# SiPM.net
KiCad netlist of a schematic drawn in EAGLE
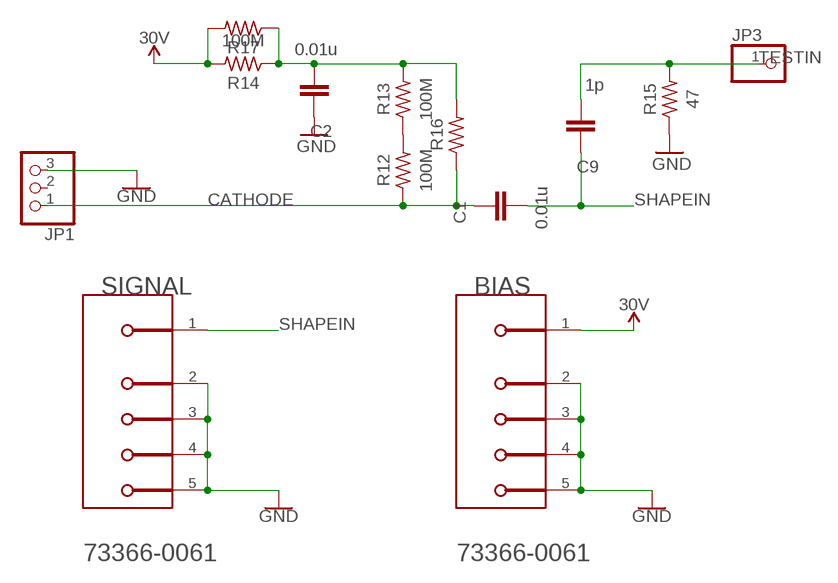
[diagram p0: schematic, sheet 1]

(export (version "E")
  (design (tool "Eeschema 10.0.6"))
  (components
    (comp (ref "BIAS")
      (value "MOLEX_73366-0061MOLEX_73366-0061_0_0")
      (footprint "eagle-import:MOLEX_73366-0061_0")
      (fields
        (field (name "DIGIKEY_PART_NUMBER") "WM5541-ND")
        (field (name "MF") "Molex")
        (field (name "MOUSER_PART_NUMBER") "538-73366-0061")
      )
      (libsource (lib "eagle-import") (part "MOLEX_73366-0061MOLEX_73366-0061_0_0"))
    )
    (comp (ref "C1")
      (value "0.01u")
      (footprint "eagle-import:CAP_1206")
      (fields
        (field (name "DIGIKEY_PART_NUMBER") "GRM31CR60J107ME39L")
        (field (name "MANUFACTURER") "Murata Electronics North America")
        (field (name "CREATED_BY") "PCBLayout.com")
      )
      (libsource (lib "eagle-import") (part "GRM31CR60J107ME39L"))
    )
    (comp (ref "C2")
      (value "0.01u")
      (footprint "eagle-import:CAP_1206")
      (fields
        (field (name "DIGIKEY_PART_NUMBER") "GRM31CR60J107ME39L")
        (field (name "MANUFACTURER") "Murata Electronics North America")
        (field (name "CREATED_BY") "PCBLayout.com")
      )
      (libsource (lib "eagle-import") (part "GRM31CR60J107ME39L"))
    )
    (comp (ref "C9")
      (value "1p")
      (footprint "eagle-import:CAP_1206")
      (fields
        (field (name "DIGIKEY_PART_NUMBER") "GRM31CR60J107ME39L")
        (field (name "MANUFACTURER") "Murata Electronics North America")
        (field (name "CREATED_BY") "PCBLayout.com")
      )
      (libsource (lib "eagle-import") (part "GRM31CR60J107ME39L"))
    )
    (comp (ref "JP1")
      (value "PINHD-1X3")
      (footprint "eagle-import:1X03")
      (libsource (lib "eagle-import") (part "PINHD-1X3"))
    )
    (comp (ref "JP3")
      (value "PINHD-1X1")
      (footprint "eagle-import:1X01")
      (libsource (lib "eagle-import") (part "PINHD-1X1"))
    )
    (comp (ref "R12")
      (value "100M")
      (footprint "eagle-import:RESAD1176W63L850D250B")
      (libsource (lib "eagle-import") (part "R-USAXIAL-11.7MM-PITCH_"))
    )
    (comp (ref "R13")
      (value "100M")
      (footprint "eagle-import:RESAD1176W63L850D250B")
      (libsource (lib "eagle-import") (part "R-USAXIAL-11.7MM-PITCH_"))
    )
    (comp (ref "R14")
      (value "100M")
      (footprint "eagle-import:RESAD1176W63L850D250B")
      (libsource (lib "eagle-import") (part "R-USAXIAL-11.7MM-PITCH_"))
    )
    (comp (ref "R15")
      (value "47")
      (footprint "eagle-import:RESAD1176W63L850D250B")
      (libsource (lib "eagle-import") (part "R-USAXIAL-11.7MM-PITCH_"))
    )
    (comp (ref "R16")
      (value "R-US_AXIAL-11.7MM-PITCH")
      (footprint "eagle-import:RESAD1176W63L850D250B")
      (libsource (lib "eagle-import") (part "R-USAXIAL-11.7MM-PITCH_"))
    )
    (comp (ref "R17")
      (value "R-US_AXIAL-11.7MM-PITCH")
      (footprint "eagle-import:RESAD1176W63L850D250B")
      (libsource (lib "eagle-import") (part "R-USAXIAL-11.7MM-PITCH_"))
    )
    (comp (ref "SIGNAL")
      (value "MOLEX_73366-0061MOLEX_73366-0061_0_0")
      (footprint "eagle-import:MOLEX_73366-0061_0")
      (fields
        (field (name "DIGIKEY_PART_NUMBER") "WM5541-ND")
        (field (name "MF") "Molex")
        (field (name "MOUSER_PART_NUMBER") "538-73366-0061")
      )
      (libsource (lib "eagle-import") (part "MOLEX_73366-0061MOLEX_73366-0061_0_0"))
    )
  )
  (nets
    (net (code "1") (name "/CATHODE") (class "Default")
      (node (ref "C1") (pin "1") (pinfunction "1_1") (pintype "passive"))
      (node (ref "JP1") (pin "1") (pinfunction "1_1") (pintype "passive"))
      (node (ref "R12") (pin "1") (pinfunction "1_1") (pintype "passive"))
      (node (ref "R16") (pin "1") (pinfunction "1_1") (pintype "passive"))
    )
    (net (code "2") (name "/SHAPEIN") (class "Default")
      (node (ref "C1") (pin "2") (pinfunction "2_2") (pintype "passive"))
      (node (ref "C9") (pin "1") (pinfunction "1_1") (pintype "passive"))
      (node (ref "SIGNAL") (pin "1") (pinfunction "1_1") (pintype "passive"))
    )
    (net (code "3") (name "/TESTIN") (class "Default")
      (node (ref "C9") (pin "2") (pinfunction "2_2") (pintype "passive"))
      (node (ref "JP3") (pin "1") (pinfunction "1_1") (pintype "passive"))
      (node (ref "R15") (pin "2") (pinfunction "2_2") (pintype "passive"))
    )
    (net (code "4") (name "30V") (class "Default")
      (node (ref "BIAS") (pin "1") (pinfunction "1_1") (pintype "passive"))
      (node (ref "R14") (pin "2") (pinfunction "2_2") (pintype "passive"))
      (node (ref "R17") (pin "2") (pinfunction "2_2") (pintype "passive"))
    )
    (net (code "5") (name "GND") (class "Default")
      (node (ref "BIAS") (pin "2") (pinfunction "MNT_1_2") (pintype "passive"))
      (node (ref "BIAS") (pin "3") (pinfunction "MNT_2_3") (pintype "passive"))
      (node (ref "BIAS") (pin "4") (pinfunction "MNT_3_4") (pintype "passive"))
      (node (ref "BIAS") (pin "5") (pinfunction "MNT_4_5") (pintype "passive"))
      (node (ref "C2") (pin "1") (pinfunction "1_1") (pintype "passive"))
      (node (ref "JP1") (pin "3") (pinfunction "3_3") (pintype "passive"))
      (node (ref "R15") (pin "1") (pinfunction "1_1") (pintype "passive"))
      (node (ref "SIGNAL") (pin "2") (pinfunction "MNT_1_2") (pintype "passive"))
      (node (ref "SIGNAL") (pin "3") (pinfunction "MNT_2_3") (pintype "passive"))
      (node (ref "SIGNAL") (pin "4") (pinfunction "MNT_3_4") (pintype "passive"))
      (node (ref "SIGNAL") (pin "5") (pinfunction "MNT_4_5") (pintype "passive"))
    )
    (net (code "6") (name "Net-(C2-Pad2)") (class "Default")
      (node (ref "C2") (pin "2") (pinfunction "2_2") (pintype "passive"))
      (node (ref "R13") (pin "2") (pinfunction "2_2") (pintype "passive"))
      (node (ref "R14") (pin "1") (pinfunction "1_1") (pintype "passive"))
      (node (ref "R16") (pin "2") (pinfunction "2_2") (pintype "passive"))
      (node (ref "R17") (pin "1") (pinfunction "1_1") (pintype "passive"))
    )
    (net (code "7") (name "Net-(R12-Pad2)") (class "Default")
      (node (ref "R12") (pin "2") (pinfunction "2_2") (pintype "passive"))
      (node (ref "R13") (pin "1") (pinfunction "1_1") (pintype "passive"))
    )
    (net (code "8") (name "unconnected-(JP1-Pad2)") (class "Default")
      (node (ref "JP1") (pin "2") (pinfunction "2_2") (pintype "passive"))
    )
  )
)
